# Le-Board.net
KiCad netlist of a schematic drawn in EAGLE
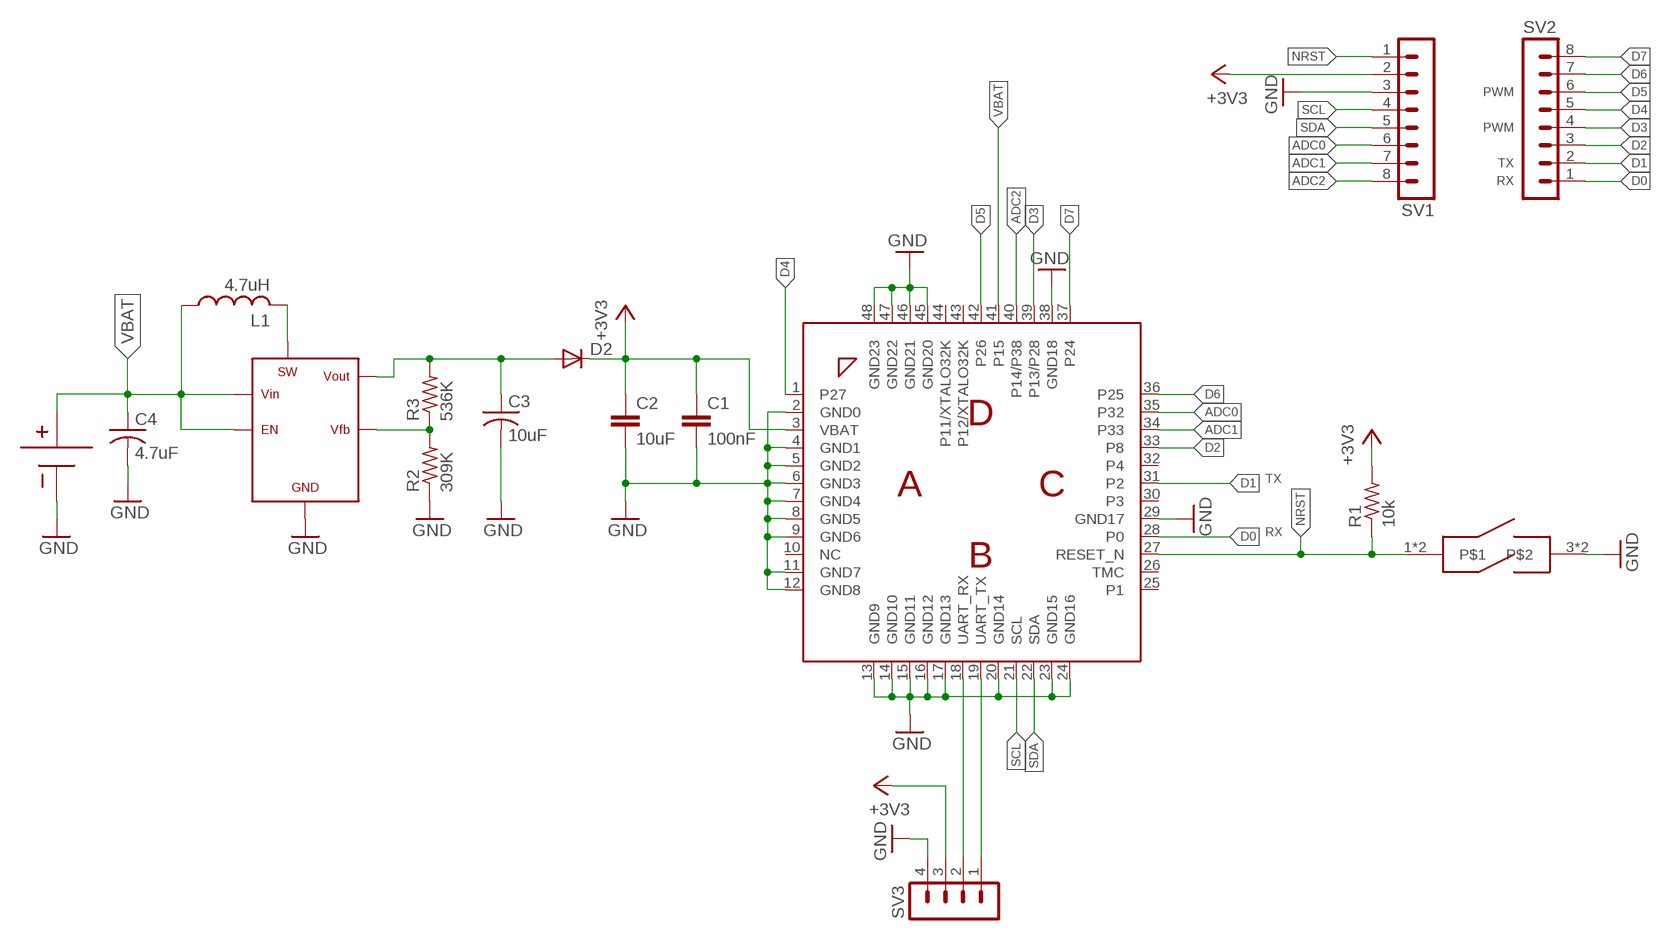
[diagram p0: schematic, sheet 1]

(export (version "E")
  (design (tool "Eeschema 10.0.6"))
  (components
    (comp (ref "C1")
      (value "100nF")
      (footprint "eagle-import:C0603")
      (libsource (lib "eagle-import") (part "C-EUC0603"))
    )
    (comp (ref "C2")
      (value "10uF")
      (footprint "eagle-import:C0603")
      (libsource (lib "eagle-import") (part "C-EUC0603"))
    )
    (comp (ref "C3")
      (value "10uF")
      (footprint "eagle-import:C0603")
      (libsource (lib "eagle-import") (part "C-USC0603"))
    )
    (comp (ref "C4")
      (value "4.7uF")
      (footprint "eagle-import:C0603")
      (libsource (lib "eagle-import") (part "C-USC0603"))
    )
    (comp (ref "D2")
      (value "DIODE-DO214AA")
      (footprint "eagle-import:DO214AA")
      (libsource (lib "eagle-import") (part "DIODE-DO214AA"))
    )
    (comp (ref "L1")
      (value "4.7uH")
      (footprint "eagle-import:L2825P")
      (libsource (lib "eagle-import") (part "L-USL2825P"))
    )
    (comp (ref "R1")
      (value "10k")
      (footprint "eagle-import:R0603")
      (libsource (lib "eagle-import") (part "R-US_R0603"))
    )
    (comp (ref "R2")
      (value "309K")
      (footprint "eagle-import:R0603")
      (libsource (lib "eagle-import") (part "R-US_R0603"))
    )
    (comp (ref "R3")
      (value "536K")
      (footprint "eagle-import:R0603")
      (libsource (lib "eagle-import") (part "R-US_R0603"))
    )
    (comp (ref "SV1")
      (value "MA08-1")
      (footprint "eagle-import:MA08-1")
      (libsource (lib "eagle-import") (part "MA08-1"))
    )
    (comp (ref "SV2")
      (value "MA08-1")
      (footprint "eagle-import:MA08-1")
      (libsource (lib "eagle-import") (part "MA08-1"))
    )
    (comp (ref "SV3")
      (value "MA04-1")
      (footprint "eagle-import:MA04-1")
      (libsource (lib "eagle-import") (part "MA04-1"))
    )
    (comp (ref "U$1")
      (value "BCM20732S")
      (footprint "eagle-import:LGA-48")
      (libsource (lib "eagle-import") (part "BCM20732S"))
    )
    (comp (ref "U$5")
      (value "ELEVATOR")
      (footprint "eagle-import:ELEVATOR")
      (libsource (lib "eagle-import") (part "ELEVATOR"))
    )
    (comp (ref "U$10")
      (value "FSM4JSMA")
      (footprint "eagle-import:FSM4JSMA")
      (libsource (lib "eagle-import") (part "FSM4JSMA"))
    )
    (comp (ref "U$17")
      (value "CR2032_HLD")
      (footprint "eagle-import:CR2031_BAT_HLD")
      (libsource (lib "eagle-import") (part "CR2032_HLD"))
    )
  )
  (nets
    (net (code "1") (name "+3V3") (class "Default")
      (node (ref "C1") (pin "1") (pinfunction "1_1") (pintype "passive"))
      (node (ref "C2") (pin "1") (pinfunction "1_1") (pintype "passive"))
      (node (ref "D2") (pin "C") (pinfunction "C_C") (pintype "passive"))
      (node (ref "R1") (pin "2") (pinfunction "2_2") (pintype "passive"))
      (node (ref "SV1") (pin "2") (pinfunction "2_2") (pintype "passive"))
      (node (ref "SV3") (pin "3") (pinfunction "3_3") (pintype "passive"))
      (node (ref "U$1") (pin "3") (pinfunction "VBAT_3") (pintype "bidirectional"))
    )
    (net (code "2") (name "ADC0") (class "Default")
      (node (ref "SV1") (pin "6") (pinfunction "6_6") (pintype "passive"))
      (node (ref "U$1") (pin "35") (pinfunction "P32_35") (pintype "bidirectional"))
    )
    (net (code "3") (name "ADC1") (class "Default")
      (node (ref "SV1") (pin "7") (pinfunction "7_7") (pintype "passive"))
      (node (ref "U$1") (pin "34") (pinfunction "P33_34") (pintype "bidirectional"))
    )
    (net (code "4") (name "ADC2") (class "Default")
      (node (ref "SV1") (pin "8") (pinfunction "8_8") (pintype "passive"))
      (node (ref "U$1") (pin "40") (pinfunction "P14/P38_40") (pintype "bidirectional"))
    )
    (net (code "5") (name "D0") (class "Default")
      (node (ref "SV2") (pin "1") (pinfunction "1_1") (pintype "passive"))
      (node (ref "U$1") (pin "28") (pinfunction "P0_28") (pintype "bidirectional"))
    )
    (net (code "6") (name "D1") (class "Default")
      (node (ref "SV2") (pin "2") (pinfunction "2_2") (pintype "passive"))
      (node (ref "U$1") (pin "31") (pinfunction "P2_31") (pintype "bidirectional"))
    )
    (net (code "7") (name "D2") (class "Default")
      (node (ref "SV2") (pin "3") (pinfunction "3_3") (pintype "passive"))
      (node (ref "U$1") (pin "33") (pinfunction "P8_33") (pintype "bidirectional"))
    )
    (net (code "8") (name "D3") (class "Default")
      (node (ref "SV2") (pin "4") (pinfunction "4_4") (pintype "passive"))
      (node (ref "U$1") (pin "39") (pinfunction "P13/P28_39") (pintype "bidirectional"))
    )
    (net (code "9") (name "D4") (class "Default")
      (node (ref "SV2") (pin "5") (pinfunction "5_5") (pintype "passive"))
      (node (ref "U$1") (pin "1") (pinfunction "P27_1") (pintype "bidirectional"))
    )
    (net (code "10") (name "D5") (class "Default")
      (node (ref "SV2") (pin "6") (pinfunction "6_6") (pintype "passive"))
      (node (ref "U$1") (pin "42") (pinfunction "P26_42") (pintype "bidirectional"))
    )
    (net (code "11") (name "D6") (class "Default")
      (node (ref "SV2") (pin "7") (pinfunction "7_7") (pintype "passive"))
      (node (ref "U$1") (pin "36") (pinfunction "P25_36") (pintype "bidirectional"))
    )
    (net (code "12") (name "D7") (class "Default")
      (node (ref "SV2") (pin "8") (pinfunction "8_8") (pintype "passive"))
      (node (ref "U$1") (pin "37") (pinfunction "P24_37") (pintype "bidirectional"))
    )
    (net (code "13") (name "GND") (class "Default")
      (node (ref "C1") (pin "2") (pinfunction "2_2") (pintype "passive"))
      (node (ref "C2") (pin "2") (pinfunction "2_2") (pintype "passive"))
      (node (ref "C3") (pin "2") (pinfunction "2_2") (pintype "passive"))
      (node (ref "C4") (pin "2") (pinfunction "2_2") (pintype "passive"))
      (node (ref "R2") (pin "1") (pinfunction "1_1") (pintype "passive"))
      (node (ref "SV1") (pin "3") (pinfunction "3_3") (pintype "passive"))
      (node (ref "SV3") (pin "4") (pinfunction "4_4") (pintype "passive"))
      (node (ref "U$1") (pin "11") (pinfunction "GND7_11") (pintype "bidirectional"))
      (node (ref "U$1") (pin "12") (pinfunction "GND8_12") (pintype "bidirectional"))
      (node (ref "U$1") (pin "13") (pinfunction "GND9_13") (pintype "bidirectional"))
      (node (ref "U$1") (pin "14") (pinfunction "GND10_14") (pintype "bidirectional"))
      (node (ref "U$1") (pin "15") (pinfunction "GND11_15") (pintype "bidirectional"))
      (node (ref "U$1") (pin "16") (pinfunction "GND12_16") (pintype "bidirectional"))
      (node (ref "U$1") (pin "17") (pinfunction "GND13_17") (pintype "bidirectional"))
      (node (ref "U$1") (pin "2") (pinfunction "GND0_2") (pintype "bidirectional"))
      (node (ref "U$1") (pin "20") (pinfunction "GND14_20") (pintype "bidirectional"))
      (node (ref "U$1") (pin "23") (pinfunction "GND15_23") (pintype "bidirectional"))
      (node (ref "U$1") (pin "24") (pinfunction "GND16_24") (pintype "bidirectional"))
      (node (ref "U$1") (pin "29") (pinfunction "GND17_29") (pintype "bidirectional"))
      (node (ref "U$1") (pin "38") (pinfunction "GND18_38") (pintype "bidirectional"))
      (node (ref "U$1") (pin "4") (pinfunction "GND1_4") (pintype "bidirectional"))
      (node (ref "U$1") (pin "45") (pinfunction "GND20_45") (pintype "bidirectional"))
      (node (ref "U$1") (pin "46") (pinfunction "GND21_46") (pintype "bidirectional"))
      (node (ref "U$1") (pin "47") (pinfunction "GND22_47") (pintype "bidirectional"))
      (node (ref "U$1") (pin "48") (pinfunction "GND23_48") (pintype "bidirectional"))
      (node (ref "U$1") (pin "5") (pinfunction "GND2_5") (pintype "bidirectional"))
      (node (ref "U$1") (pin "6") (pinfunction "GND3_6") (pintype "bidirectional"))
      (node (ref "U$1") (pin "7") (pinfunction "GND4_7") (pintype "bidirectional"))
      (node (ref "U$1") (pin "8") (pinfunction "GND5_8") (pintype "bidirectional"))
      (node (ref "U$1") (pin "9") (pinfunction "GND6_9") (pintype "bidirectional"))
      (node (ref "U$10") (pin "3") (pinfunction "P$2_3") (pintype "bidirectional"))
      (node (ref "U$10") (pin "4") (pinfunction "P$2_4") (pintype "bidirectional"))
      (node (ref "U$17") (pin "BOT") (pinfunction "-_BOT") (pintype "bidirectional"))
      (node (ref "U$5") (pin "2") (pinfunction "GND_2") (pintype "bidirectional"))
    )
    (net (code "14") (name "NRST") (class "Default")
      (node (ref "R1") (pin "1") (pinfunction "1_1") (pintype "passive"))
      (node (ref "SV1") (pin "1") (pinfunction "1_1") (pintype "passive"))
      (node (ref "U$1") (pin "27") (pinfunction "RESET_N_27") (pintype "bidirectional"))
      (node (ref "U$10") (pin "1") (pinfunction "P$1_1") (pintype "bidirectional"))
      (node (ref "U$10") (pin "2") (pinfunction "P$1_2") (pintype "bidirectional"))
    )
    (net (code "15") (name "Net-(U$1-UART_RX)") (class "Default")
      (node (ref "SV3") (pin "2") (pinfunction "2_2") (pintype "passive"))
      (node (ref "U$1") (pin "18") (pinfunction "UART_RX_18") (pintype "bidirectional"))
    )
    (net (code "16") (name "Net-(U$1-UART_TX)") (class "Default")
      (node (ref "SV3") (pin "1") (pinfunction "1_1") (pintype "passive"))
      (node (ref "U$1") (pin "19") (pinfunction "UART_TX_19") (pintype "bidirectional"))
    )
    (net (code "17") (name "Net-(U$5-SW)") (class "Default")
      (node (ref "L1") (pin "2") (pinfunction "2_2") (pintype "passive"))
      (node (ref "U$5") (pin "1") (pinfunction "SW_1") (pintype "bidirectional"))
    )
    (net (code "18") (name "Net-(U$5-VFB)") (class "Default")
      (node (ref "R2") (pin "2") (pinfunction "2_2") (pintype "passive"))
      (node (ref "R3") (pin "1") (pinfunction "1_1") (pintype "passive"))
      (node (ref "U$5") (pin "4") (pinfunction "VFB_4") (pintype "bidirectional"))
    )
    (net (code "19") (name "Net-(U$5-VOUT)") (class "Default")
      (node (ref "C3") (pin "1") (pinfunction "1_1") (pintype "passive"))
      (node (ref "D2") (pin "A") (pinfunction "A_A") (pintype "passive"))
      (node (ref "R3") (pin "2") (pinfunction "2_2") (pintype "passive"))
      (node (ref "U$5") (pin "5") (pinfunction "VOUT_5") (pintype "bidirectional"))
    )
    (net (code "20") (name "SCL") (class "Default")
      (node (ref "SV1") (pin "4") (pinfunction "4_4") (pintype "passive"))
      (node (ref "U$1") (pin "21") (pinfunction "SCL_21") (pintype "bidirectional"))
    )
    (net (code "21") (name "SDA") (class "Default")
      (node (ref "SV1") (pin "5") (pinfunction "5_5") (pintype "passive"))
      (node (ref "U$1") (pin "22") (pinfunction "SDA_22") (pintype "bidirectional"))
    )
    (net (code "22") (name "VBAT") (class "Default")
      (node (ref "C4") (pin "1") (pinfunction "1_1") (pintype "passive"))
      (node (ref "L1") (pin "1") (pinfunction "1_1") (pintype "passive"))
      (node (ref "U$1") (pin "41") (pinfunction "P15_41") (pintype "bidirectional"))
      (node (ref "U$17") (pin "TOP1") (pinfunction "+_TOP1") (pintype "bidirectional"))
      (node (ref "U$17") (pin "TOP2") (pinfunction "+_TOP2") (pintype "bidirectional"))
      (node (ref "U$5") (pin "3") (pinfunction "EN_3") (pintype "bidirectional"))
      (node (ref "U$5") (pin "6") (pinfunction "VIN_6") (pintype "bidirectional"))
    )
    (net (code "23") (name "unconnected-(U$1-NC-Pad10)") (class "Default")
      (node (ref "U$1") (pin "10") (pinfunction "NC_10") (pintype "bidirectional"))
    )
    (net (code "24") (name "unconnected-(U$1-P1-Pad25)") (class "Default")
      (node (ref "U$1") (pin "25") (pinfunction "P1_25") (pintype "bidirectional"))
    )
    (net (code "25") (name "unconnected-(U$1-P3-Pad30)") (class "Default")
      (node (ref "U$1") (pin "30") (pinfunction "P3_30") (pintype "bidirectional"))
    )
    (net (code "26") (name "unconnected-(U$1-P4-Pad32)") (class "Default")
      (node (ref "U$1") (pin "32") (pinfunction "P4_32") (pintype "bidirectional"))
    )
    (net (code "27") (name "unconnected-(U$1-P11{slash}XTALO32K-Pad44)") (class "Default")
      (node (ref "U$1") (pin "44") (pinfunction "P11/XTALO32K_44") (pintype "bidirectional"))
    )
    (net (code "28") (name "unconnected-(U$1-P12{slash}XTALO32K-Pad43)") (class "Default")
      (node (ref "U$1") (pin "43") (pinfunction "P12/XTALO32K_43") (pintype "bidirectional"))
    )
    (net (code "29") (name "unconnected-(U$1-TMC-Pad26)") (class "Default")
      (node (ref "U$1") (pin "26") (pinfunction "TMC_26") (pintype "bidirectional"))
    )
  )
)
